# LilyPad_FTDI_Basic-v21-5V.net
KiCad netlist of a schematic drawn in EAGLE
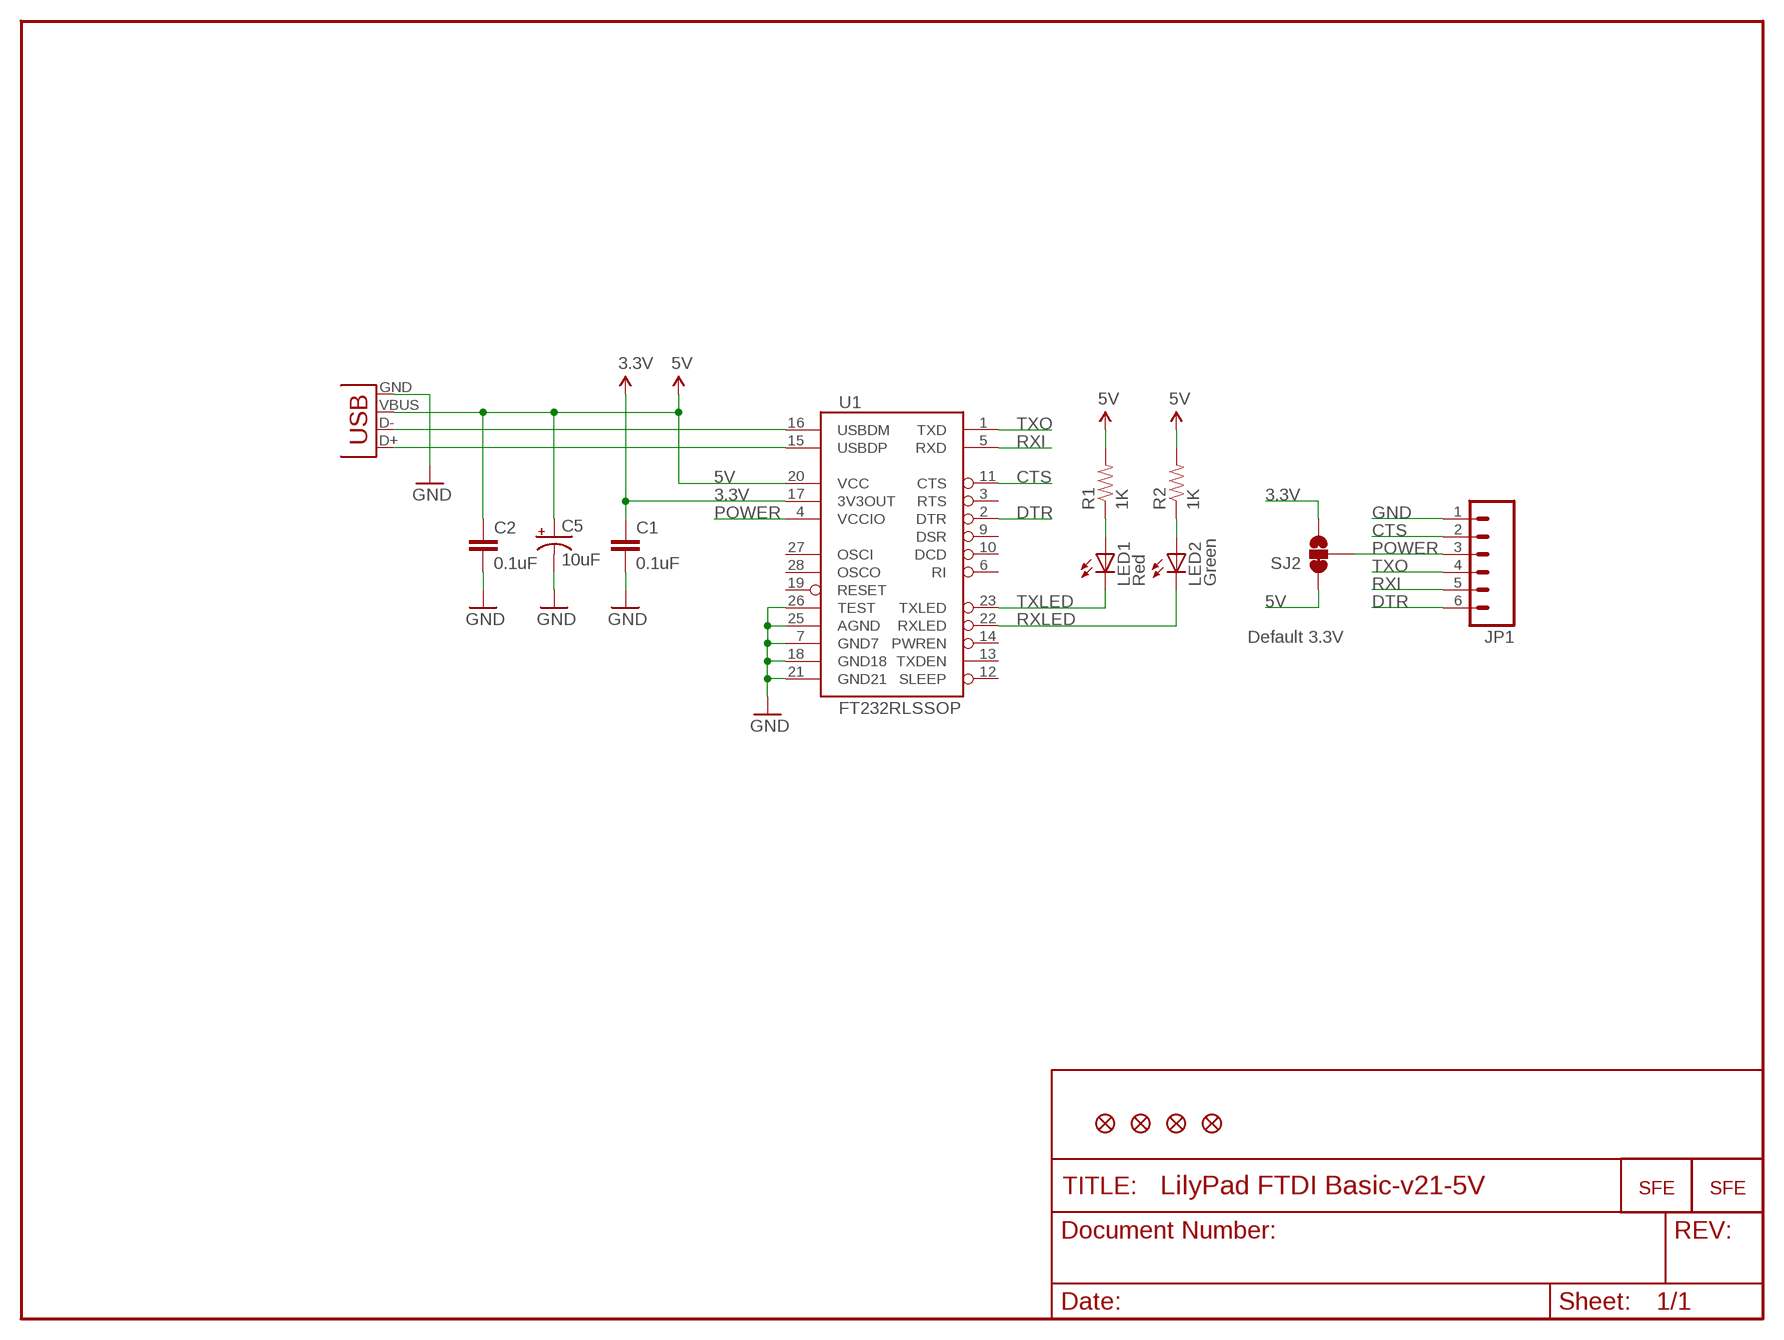
[diagram p0: schematic, sheet 1]

(export (version "E")
  (design (tool "Eeschema 10.0.6"))
  (components
    (comp (ref "C1")
      (value "0.1uF")
      (footprint "eagle-import:0805")
      (libsource (lib "eagle-import") (part "CAP0805"))
    )
    (comp (ref "C2")
      (value "0.1uF")
      (footprint "eagle-import:0805")
      (libsource (lib "eagle-import") (part "CAP0805"))
    )
    (comp (ref "C5")
      (value "10uF")
      (footprint "eagle-import:EIA3216")
      (libsource (lib "eagle-import") (part "CAP_POL1206"))
    )
    (comp (ref "JP1")
      (value "M06SMD-FEMALE-V2")
      (footprint "eagle-import:1X06-SMD-FEMALE-V2")
      (libsource (lib "eagle-import") (part "M06SMD-FEMALE-V2"))
    )
    (comp (ref "JP2")
      (value "LOGO-SFESK")
      (footprint "eagle-import:SFE-LOGO-FLAME")
      (libsource (lib "eagle-import") (part "LOGO-SFESK"))
    )
    (comp (ref "JP7")
      (value "FIDUCIAL1X2")
      (footprint "eagle-import:FIDUCIAL-1X2")
      (libsource (lib "eagle-import") (part "FIDUCIAL1X2"))
    )
    (comp (ref "JP8")
      (value "FIDUCIAL1X2")
      (footprint "eagle-import:FIDUCIAL-1X2")
      (libsource (lib "eagle-import") (part "FIDUCIAL1X2"))
    )
    (comp (ref "JP9")
      (value "FIDUCIAL1X2")
      (footprint "eagle-import:FIDUCIAL-1X2")
      (libsource (lib "eagle-import") (part "FIDUCIAL1X2"))
    )
    (comp (ref "JP10")
      (value "FIDUCIAL1X2")
      (footprint "eagle-import:FIDUCIAL-1X2")
      (libsource (lib "eagle-import") (part "FIDUCIAL1X2"))
    )
    (comp (ref "LED1")
      (value "Red")
      (footprint "eagle-import:LED-0603")
      (libsource (lib "eagle-import") (part "LED0603"))
    )
    (comp (ref "LED2")
      (value "Green")
      (footprint "eagle-import:LED-0603")
      (libsource (lib "eagle-import") (part "LED0603"))
    )
    (comp (ref "R1")
      (value "1K")
      (footprint "eagle-import:0805")
      (libsource (lib "eagle-import") (part "RESISTOR0805-RES"))
    )
    (comp (ref "R2")
      (value "1K")
      (footprint "eagle-import:0805")
      (libsource (lib "eagle-import") (part "RESISTOR0805-RES"))
    )
    (comp (ref "SJ2")
      (value "SOLDERJUMPER_2WAYS")
      (footprint "eagle-import:SJ_3")
      (libsource (lib "eagle-import") (part "SOLDERJUMPER_2WAYS"))
    )
    (comp (ref "U$2")
      (value "LOGO-SFENW2")
      (footprint "eagle-import:SFE-NEW-WEB")
      (libsource (lib "eagle-import") (part "LOGO-SFENW2"))
    )
    (comp (ref "U1")
      (value "FT232RLSSOP")
      (footprint "eagle-import:SSOP28DB")
      (libsource (lib "eagle-import") (part "FT232RLSSOP"))
    )
    (comp (ref "X2")
      (value "USB-SMD-NS")
      (footprint "eagle-import:USB-MINIB-NOSTOP")
      (libsource (lib "eagle-import") (part "USB-SMD-NS"))
    )
  )
  (nets
    (net (code "1") (name "/CTS") (class "Default")
      (node (ref "JP1") (pin "2") (pinfunction "2_2") (pintype "passive"))
      (node (ref "U1") (pin "11") (pinfunction "CTS_11") (pintype "input"))
    )
    (net (code "2") (name "/DTR") (class "Default")
      (node (ref "JP1") (pin "6") (pinfunction "6_6") (pintype "passive"))
      (node (ref "U1") (pin "2") (pinfunction "DTR_2") (pintype "output"))
    )
    (net (code "3") (name "/POWER") (class "Default")
      (node (ref "JP1") (pin "3") (pinfunction "3_3") (pintype "passive"))
      (node (ref "SJ2") (pin "2") (pinfunction "2_2") (pintype "passive"))
      (node (ref "U1") (pin "4") (pinfunction "VCCIO_4") (pintype "power_in"))
    )
    (net (code "4") (name "/RXI") (class "Default")
      (node (ref "JP1") (pin "5") (pinfunction "5_5") (pintype "passive"))
      (node (ref "U1") (pin "5") (pinfunction "RXD_5") (pintype "input"))
    )
    (net (code "5") (name "/RXLED") (class "Default")
      (node (ref "LED2") (pin "C") (pinfunction "C_C") (pintype "passive"))
      (node (ref "U1") (pin "22") (pinfunction "RXLED_22") (pintype "input"))
    )
    (net (code "6") (name "/TXLED") (class "Default")
      (node (ref "LED1") (pin "C") (pinfunction "C_C") (pintype "passive"))
      (node (ref "U1") (pin "23") (pinfunction "TXLED_23") (pintype "input"))
    )
    (net (code "7") (name "/TXO") (class "Default")
      (node (ref "JP1") (pin "4") (pinfunction "4_4") (pintype "passive"))
      (node (ref "U1") (pin "1") (pinfunction "TXD_1") (pintype "output"))
    )
    (net (code "8") (name "3.3V") (class "Default")
      (node (ref "C1") (pin "1") (pinfunction "1_1") (pintype "passive"))
      (node (ref "SJ2") (pin "3") (pinfunction "3_3") (pintype "passive"))
      (node (ref "U1") (pin "17") (pinfunction "3V3OUT_17") (pintype "output"))
    )
    (net (code "9") (name "5V") (class "Default")
      (node (ref "C2") (pin "1") (pinfunction "1_1") (pintype "passive"))
      (node (ref "C5") (pin "A") (pinfunction "+_A") (pintype "passive"))
      (node (ref "R1") (pin "2") (pinfunction "2_2") (pintype "passive"))
      (node (ref "R2") (pin "2") (pinfunction "2_2") (pintype "passive"))
      (node (ref "SJ2") (pin "1") (pinfunction "1_1") (pintype "passive"))
      (node (ref "U1") (pin "20") (pinfunction "VCC_20") (pintype "power_in"))
      (node (ref "X2") (pin "VBUS") (pinfunction "VBUS_VBUS") (pintype "bidirectional"))
    )
    (net (code "10") (name "GND") (class "Default")
      (node (ref "C1") (pin "2") (pinfunction "2_2") (pintype "passive"))
      (node (ref "C2") (pin "2") (pinfunction "2_2") (pintype "passive"))
      (node (ref "C5") (pin "C") (pinfunction "-_C") (pintype "passive"))
      (node (ref "JP1") (pin "1") (pinfunction "1_1") (pintype "passive"))
      (node (ref "U1") (pin "18") (pinfunction "GND18_18") (pintype "power_in"))
      (node (ref "U1") (pin "21") (pinfunction "GND21_21") (pintype "power_in"))
      (node (ref "U1") (pin "25") (pinfunction "AGND_25") (pintype "power_in"))
      (node (ref "U1") (pin "26") (pinfunction "TEST_26") (pintype "input"))
      (node (ref "U1") (pin "7") (pinfunction "GND7_7") (pintype "power_in"))
      (node (ref "X2") (pin "GND") (pinfunction "GND_GND") (pintype "bidirectional"))
    )
    (net (code "11") (name "Net-(LED1-PadA)") (class "Default")
      (node (ref "LED1") (pin "A") (pinfunction "A_A") (pintype "passive"))
      (node (ref "R1") (pin "1") (pinfunction "1_1") (pintype "passive"))
    )
    (net (code "12") (name "Net-(LED2-PadA)") (class "Default")
      (node (ref "LED2") (pin "A") (pinfunction "A_A") (pintype "passive"))
      (node (ref "R2") (pin "1") (pinfunction "1_1") (pintype "passive"))
    )
    (net (code "13") (name "Net-(U1-USBDM)") (class "Default")
      (node (ref "U1") (pin "16") (pinfunction "USBDM_16") (pintype "bidirectional"))
      (node (ref "X2") (pin "D-") (pinfunction "D-_D-") (pintype "bidirectional"))
    )
    (net (code "14") (name "Net-(U1-USBDP)") (class "Default")
      (node (ref "U1") (pin "15") (pinfunction "USBDP_15") (pintype "bidirectional"))
      (node (ref "X2") (pin "D+") (pinfunction "D+_D+") (pintype "bidirectional"))
    )
    (net (code "15") (name "unconnected-(U1-DCD-Pad10)") (class "Default")
      (node (ref "U1") (pin "10") (pinfunction "DCD_10") (pintype "input"))
    )
    (net (code "16") (name "unconnected-(U1-DSR-Pad9)") (class "Default")
      (node (ref "U1") (pin "9") (pinfunction "DSR_9") (pintype "input"))
    )
    (net (code "17") (name "unconnected-(U1-OSCI-Pad27)") (class "Default")
      (node (ref "U1") (pin "27") (pinfunction "OSCI_27") (pintype "input"))
    )
    (net (code "18") (name "unconnected-(U1-OSCO-Pad28)") (class "Default")
      (node (ref "U1") (pin "28") (pinfunction "OSCO_28") (pintype "output"))
    )
    (net (code "19") (name "unconnected-(U1-PWREN-Pad14)") (class "Default")
      (node (ref "U1") (pin "14") (pinfunction "PWREN_14") (pintype "input"))
    )
    (net (code "20") (name "unconnected-(U1-RESET-Pad19)") (class "Default")
      (node (ref "U1") (pin "19") (pinfunction "RESET_19") (pintype "input"))
    )
    (net (code "21") (name "unconnected-(U1-RI-Pad6)") (class "Default")
      (node (ref "U1") (pin "6") (pinfunction "RI_6") (pintype "input"))
    )
    (net (code "22") (name "unconnected-(U1-RTS-Pad3)") (class "Default")
      (node (ref "U1") (pin "3") (pinfunction "RTS_3") (pintype "output"))
    )
    (net (code "23") (name "unconnected-(U1-SLEEP-Pad12)") (class "Default")
      (node (ref "U1") (pin "12") (pinfunction "SLEEP_12") (pintype "input"))
    )
    (net (code "24") (name "unconnected-(U1-TXDEN-Pad13)") (class "Default")
      (node (ref "U1") (pin "13") (pinfunction "TXDEN_13") (pintype "input"))
    )
  )
)
